# not.net
KiCad netlist of a schematic drawn in Altium Designer
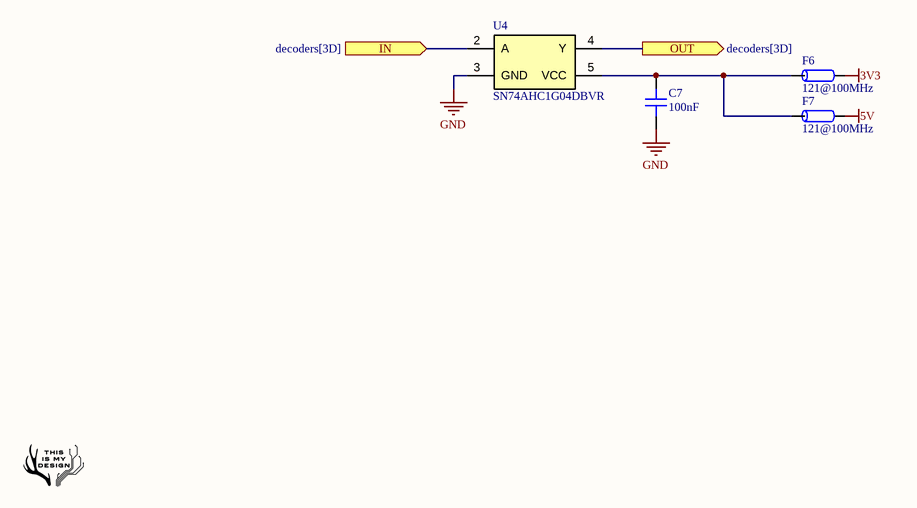
[diagram p0: not.SchDoc]

(export (version "E")
  (design (tool "Eeschema 10.0.6"))
  (components
    (comp (ref "C7")
      (value "100nF")
      (footprint "CAP 0603_1608")
      (description "SMT Capacitor")
      (libsource (lib "Capacitor") (part "Cap 0603"))
    )
    (comp (ref "F6")
      (value "121@100MHz")
      (footprint "Ferrite-0805")
      (description "Ferrite Bead")
      (libsource (lib "Salman_lib") (part "Ferrite Bead"))
    )
    (comp (ref "F7")
      (value "121@100MHz")
      (footprint "Ferrite-0805")
      (description "Ferrite Bead")
      (libsource (lib "Salman_lib") (part "Ferrite Bead"))
    )
    (comp (ref "U4")
      (value "SN74AHC1G04DBVR")
      (footprint "SOT23-5L")
      (description "Single input NOT gate")
      (libsource (lib "Salman_lib") (part "SN74AHC1G04"))
    )
  )
  (nets
    (net (code "1") (name "/IN") (class "Default")
      (node (ref "U4") (pin "2") (pinfunction "A_2") (pintype "passive"))
    )
    (net (code "2") (name "/OUT") (class "Default")
      (node (ref "U4") (pin "4") (pinfunction "Y_4") (pintype "passive"))
    )
    (net (code "3") (name "3V3") (class "Default")
      (node (ref "F6") (pin "1") (pinfunction "67_1") (pintype "passive"))
    )
    (net (code "4") (name "5V") (class "Default")
      (node (ref "F7") (pin "1") (pinfunction "67_1") (pintype "passive"))
    )
    (net (code "5") (name "GND") (class "Default")
      (node (ref "C7") (pin "1") (pinfunction "1_1") (pintype "passive"))
      (node (ref "U4") (pin "3") (pinfunction "GND_3") (pintype "passive"))
    )
    (net (code "6") (name "Net-(F6-66)") (class "Default")
      (node (ref "C7") (pin "2") (pinfunction "2_2") (pintype "passive"))
      (node (ref "F6") (pin "2") (pinfunction "66_2") (pintype "passive"))
      (node (ref "F7") (pin "2") (pinfunction "66_2") (pintype "passive"))
      (node (ref "U4") (pin "5") (pinfunction "VCC_5") (pintype "passive"))
    )
  )
)
